# 1.net
KiCad netlist of a schematic drawn in Altium Designer
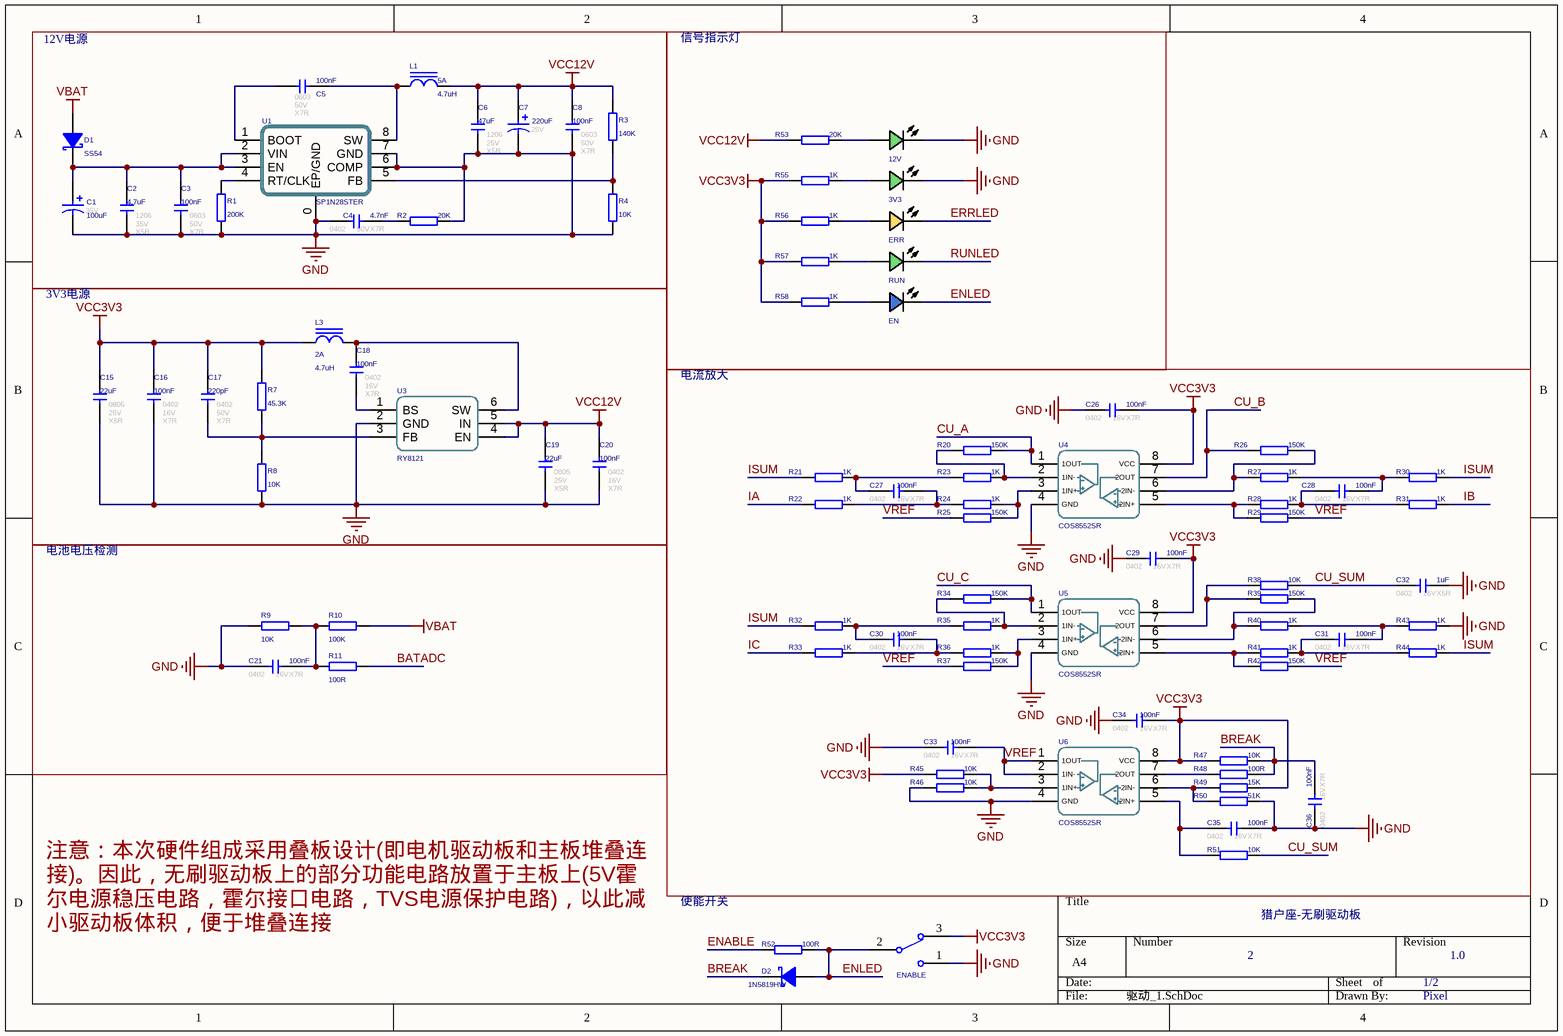
[diagram p0: 驱动_1.SchDoc]

(export (version "E")
  (design (tool "Eeschema 10.0.6"))
  (components
    (comp (ref "3V3")
      (value "翠绿贴片LED")
      (footprint "LEDC1608(0603)-L")
      (fields (field (name "PUBLISHER") "Altium Limited"))
      (libsource (lib "无刷驱动-Infineon-AUIRS2181S-GTM-6S") (part "LED Chip Green"))
    )
    (comp (ref "12V")
      (value "翠绿贴片LED")
      (footprint "LEDC1608(0603)-L")
      (fields (field (name "PUBLISHER") "Altium Limited"))
      (libsource (lib "无刷驱动-Infineon-AUIRS2181S-GTM-6S") (part "LED Chip Green"))
    )
    (comp (ref "C1")
      (value "100uF")
      (footprint "CAP-E-S 6.3")
      (description "贴片电解电容 100uF 35V 6.3x7.7")
      (fields (field (name "VOLTAGE") "35V") (field (name "Comment") "100uF 35V 铝电解"))
      (libsource (lib "无刷驱动-Infineon-AUIRS2181S-GTM-6S") (part "E-S 100uF 35V 6.3x7.7"))
    )
    (comp (ref "C2")
      (value "4.7uF")
      (footprint "1206")
      (description "贴片瓷片电容; MLCC; 1206(3216);")
      (fields
        (field (name "VOLTAGE") "35V")
        (field (name "TYPE") "X5R")
        (field (name "Comment") "4.7uF 35V X5R")
      )
      (libsource (lib "无刷驱动-Infineon-AUIRS2181S-GTM-6S") (part "4.7uF 1206 35V X5R"))
    )
    (comp (ref "C3")
      (value "100nF")
      (footprint "0603")
      (description "贴片瓷片电容; MLCC; 0603(1608);")
      (fields
        (field (name "VOLTAGE") "50V")
        (field (name "TYPE") "X7R")
        (field (name "Comment") "100nF 50V X7R")
      )
      (libsource (lib "无刷驱动-Infineon-AUIRS2181S-GTM-6S") (part "100nF 0603 50V X7R"))
    )
    (comp (ref "C4")
      (value "4.7nF")
      (footprint "0402")
      (description "贴片瓷片电容; MLCC; 0402(1005);")
      (fields
        (field (name "VOLTAGE") "50V")
        (field (name "TYPE") "X7R")
        (field (name "Comment") "4.7nF 50V X7R")
      )
      (libsource (lib "无刷驱动-Infineon-AUIRS2181S-GTM-6S") (part "4.7nF 0402 50V X7R"))
    )
    (comp (ref "C5")
      (value "100nF")
      (footprint "0603")
      (description "贴片瓷片电容; MLCC; 0603(1608);")
      (fields
        (field (name "VOLTAGE") "50V")
        (field (name "TYPE") "X7R")
        (field (name "Comment") "100nF 50V X7R")
      )
      (libsource (lib "无刷驱动-Infineon-AUIRS2181S-GTM-6S") (part "100nF 0603 50V X7R"))
    )
    (comp (ref "C6")
      (value "47uF")
      (footprint "1206")
      (description "贴片瓷片电容; MLCC; 1206(3216);")
      (fields
        (field (name "VOLTAGE") "25V")
        (field (name "TYPE") "X5R")
        (field (name "Comment") "47uF 25V X5R")
      )
      (libsource (lib "无刷驱动-Infineon-AUIRS2181S-GTM-6S") (part "47uF 1206 25V X5R"))
    )
    (comp (ref "C7")
      (value "220uF")
      (footprint "CAP-E-S 6.3")
      (description "贴片电解电容 220uF 25V 6.3x7.7")
      (fields (field (name "VOLTAGE") "25V") (field (name "Comment") "220uF 25V 铝电解"))
      (libsource (lib "无刷驱动-Infineon-AUIRS2181S-GTM-6S") (part "E-S 220uF 25V 6.3x7.7"))
    )
    (comp (ref "C8")
      (value "100nF")
      (footprint "0603")
      (description "贴片瓷片电容; MLCC; 0603(1608);")
      (fields
        (field (name "VOLTAGE") "50V")
        (field (name "TYPE") "X7R")
        (field (name "Comment") "100nF 50V X7R")
      )
      (libsource (lib "无刷驱动-Infineon-AUIRS2181S-GTM-6S") (part "100nF 0603 50V X7R"))
    )
    (comp (ref "C15")
      (value "22uF")
      (footprint "0805")
      (description "贴片瓷片电容; MLCC; 0805(2012);")
      (fields
        (field (name "VOLTAGE") "25V")
        (field (name "TYPE") "X5R")
        (field (name "Comment") "22uF 25V X5R")
      )
      (libsource (lib "无刷驱动-Infineon-AUIRS2181S-GTM-6S") (part "22uF 0805 25V X5R"))
    )
    (comp (ref "C16")
      (value "100nF")
      (footprint "0402")
      (description "贴片瓷片电容; MLCC; 0402(1005);")
      (fields
        (field (name "VOLTAGE") "16V")
        (field (name "TYPE") "X7R")
        (field (name "Comment") "100nF 16V X7R")
      )
      (libsource (lib "无刷驱动-Infineon-AUIRS2181S-GTM-6S") (part "100nF 0402 16V X7R"))
    )
    (comp (ref "C17")
      (value "220pF")
      (footprint "0402")
      (description "贴片瓷片电容; MLCC; 0402(1005);")
      (fields
        (field (name "VOLTAGE") "50V")
        (field (name "TYPE") "X7R")
        (field (name "Comment") "220pF 50V X7R")
      )
      (libsource (lib "无刷驱动-Infineon-AUIRS2181S-GTM-6S") (part "220pF 0402 50V X7R"))
    )
    (comp (ref "C18")
      (value "100nF")
      (footprint "0402")
      (description "贴片瓷片电容; MLCC; 0402(1005);")
      (fields
        (field (name "VOLTAGE") "16V")
        (field (name "TYPE") "X7R")
        (field (name "Comment") "100nF 16V X7R")
      )
      (libsource (lib "无刷驱动-Infineon-AUIRS2181S-GTM-6S") (part "100nF 0402 16V X7R"))
    )
    (comp (ref "C19")
      (value "22uF")
      (footprint "0805")
      (description "贴片瓷片电容; MLCC; 0805(2012);")
      (fields
        (field (name "VOLTAGE") "25V")
        (field (name "TYPE") "X5R")
        (field (name "Comment") "22uF 25V X5R")
      )
      (libsource (lib "无刷驱动-Infineon-AUIRS2181S-GTM-6S") (part "22uF 0805 25V X5R"))
    )
    (comp (ref "C20")
      (value "100nF")
      (footprint "0402")
      (description "贴片瓷片电容; MLCC; 0402(1005);")
      (fields
        (field (name "VOLTAGE") "16V")
        (field (name "TYPE") "X7R")
        (field (name "Comment") "100nF 16V X7R")
      )
      (libsource (lib "无刷驱动-Infineon-AUIRS2181S-GTM-6S") (part "100nF 0402 16V X7R"))
    )
    (comp (ref "C21")
      (value "100nF")
      (footprint "0402")
      (description "贴片瓷片电容; MLCC; 0402(1005);")
      (fields
        (field (name "VOLTAGE") "16V")
        (field (name "TYPE") "X7R")
        (field (name "Comment") "100nF 16V X7R")
      )
      (libsource (lib "无刷驱动-Infineon-AUIRS2181S-GTM-6S") (part "100nF 0402 16V X7R"))
    )
    (comp (ref "C26")
      (value "100nF")
      (footprint "0402")
      (description "贴片瓷片电容; MLCC; 0402(1005);")
      (fields
        (field (name "VOLTAGE") "16V")
        (field (name "TYPE") "X7R")
        (field (name "Comment") "100nF 16V X7R")
      )
      (libsource (lib "无刷驱动-Infineon-AUIRS2181S-GTM-6S") (part "100nF 0402 16V X7R"))
    )
    (comp (ref "C27")
      (value "100nF")
      (footprint "0402")
      (description "贴片瓷片电容; MLCC; 0402(1005);")
      (fields
        (field (name "VOLTAGE") "16V")
        (field (name "TYPE") "X7R")
        (field (name "Comment") "100nF 16V X7R")
      )
      (libsource (lib "无刷驱动-Infineon-AUIRS2181S-GTM-6S") (part "100nF 0402 16V X7R"))
    )
    (comp (ref "C28")
      (value "100nF")
      (footprint "0402")
      (description "贴片瓷片电容; MLCC; 0402(1005);")
      (fields
        (field (name "VOLTAGE") "16V")
        (field (name "TYPE") "X7R")
        (field (name "Comment") "100nF 16V X7R")
      )
      (libsource (lib "无刷驱动-Infineon-AUIRS2181S-GTM-6S") (part "100nF 0402 16V X7R"))
    )
    (comp (ref "C29")
      (value "100nF")
      (footprint "0402")
      (description "贴片瓷片电容; MLCC; 0402(1005);")
      (fields
        (field (name "VOLTAGE") "16V")
        (field (name "TYPE") "X7R")
        (field (name "Comment") "100nF 16V X7R")
      )
      (libsource (lib "无刷驱动-Infineon-AUIRS2181S-GTM-6S") (part "100nF 0402 16V X7R"))
    )
    (comp (ref "C30")
      (value "100nF")
      (footprint "0402")
      (description "贴片瓷片电容; MLCC; 0402(1005);")
      (fields
        (field (name "VOLTAGE") "16V")
        (field (name "TYPE") "X7R")
        (field (name "Comment") "100nF 16V X7R")
      )
      (libsource (lib "无刷驱动-Infineon-AUIRS2181S-GTM-6S") (part "100nF 0402 16V X7R"))
    )
    (comp (ref "C31")
      (value "100nF")
      (footprint "0402")
      (description "贴片瓷片电容; MLCC; 0402(1005);")
      (fields
        (field (name "VOLTAGE") "16V")
        (field (name "TYPE") "X7R")
        (field (name "Comment") "100nF 16V X7R")
      )
      (libsource (lib "无刷驱动-Infineon-AUIRS2181S-GTM-6S") (part "100nF 0402 16V X7R"))
    )
    (comp (ref "C32")
      (value "1uF")
      (footprint "0402")
      (description "贴片瓷片电容; MLCC; 0402(1005);")
      (fields
        (field (name "VOLTAGE") "16V")
        (field (name "TYPE") "X5R")
        (field (name "Comment") "1uF 16V X5R")
      )
      (libsource (lib "无刷驱动-Infineon-AUIRS2181S-GTM-6S") (part "1uF 0402 16V X5R"))
    )
    (comp (ref "C33")
      (value "100nF")
      (footprint "0402")
      (description "贴片瓷片电容; MLCC; 0402(1005);")
      (fields
        (field (name "VOLTAGE") "16V")
        (field (name "TYPE") "X7R")
        (field (name "Comment") "100nF 16V X7R")
      )
      (libsource (lib "无刷驱动-Infineon-AUIRS2181S-GTM-6S") (part "100nF 0402 16V X7R"))
    )
    (comp (ref "C34")
      (value "100nF")
      (footprint "0402")
      (description "贴片瓷片电容; MLCC; 0402(1005);")
      (fields
        (field (name "VOLTAGE") "16V")
        (field (name "TYPE") "X7R")
        (field (name "Comment") "100nF 16V X7R")
      )
      (libsource (lib "无刷驱动-Infineon-AUIRS2181S-GTM-6S") (part "100nF 0402 16V X7R"))
    )
    (comp (ref "C35")
      (value "100nF")
      (footprint "0402")
      (description "贴片瓷片电容; MLCC; 0402(1005);")
      (fields
        (field (name "VOLTAGE") "16V")
        (field (name "TYPE") "X7R")
        (field (name "Comment") "100nF 16V X7R")
      )
      (libsource (lib "无刷驱动-Infineon-AUIRS2181S-GTM-6S") (part "100nF 0402 16V X7R"))
    )
    (comp (ref "C36")
      (value "100nF")
      (footprint "0402")
      (description "贴片瓷片电容; MLCC; 0402(1005);")
      (fields
        (field (name "VOLTAGE") "16V")
        (field (name "TYPE") "X7R")
        (field (name "Comment") "100nF 16V X7R")
      )
      (libsource (lib "无刷驱动-Infineon-AUIRS2181S-GTM-6S") (part "100nF 0402 16V X7R"))
    )
    (comp (ref "D1")
      (value "SS54")
      (footprint "SMA-L[DO-214AC]")
      (description "SS54 肖特基二极管")
      (libsource (lib "无刷驱动-Infineon-AUIRS2181S-GTM-6S") (part "SS54"))
    )
    (comp (ref "D2")
      (value "1N5819HW")
      (footprint "SOD-123-L")
      (description "1N5819HW 肖特基二极管")
      (libsource (lib "无刷驱动-Infineon-AUIRS2181S-GTM-6S") (part "1N5819HW"))
    )
    (comp (ref "EN")
      (value "蓝色贴片LED")
      (footprint "LEDC1608(0603)-L")
      (fields (field (name "PUBLISHER") "Altium Limited"))
      (libsource (lib "无刷驱动-Infineon-AUIRS2181S-GTM-6S") (part "LED Chip Blue"))
    )
    (comp (ref "ENABLE")
      (value "SW-SPDT")
      (footprint "SS12D10")
      (description "单刀双掷开关 3脚船型、钮子、拨动开关 SPDT Subminiature Toggle Switch")
      (fields (field (name "PUBLISHER") "Altium Limited"))
      (libsource (lib "无刷驱动-Infineon-AUIRS2181S-GTM-6S") (part "SW-SPDT"))
    )
    (comp (ref "ERR")
      (value "黄色贴片LED")
      (footprint "LEDC1608(0603)-L")
      (fields (field (name "PUBLISHER") "Altium Limited"))
      (libsource (lib "无刷驱动-Infineon-AUIRS2181S-GTM-6S") (part "LED Chip Yellow"))
    )
    (comp (ref "L1")
      (value "4.7uH")
      (footprint "SLO2520")
      (description "功率电感")
      (fields
        (field (name "IMAX") "5A")
        (field (name "Comment") "4.7uH 5A")
        (field (name "PUBLISHER") "Altium Limited")
      )
      (libsource (lib "无刷驱动-Infineon-AUIRS2181S-GTM-6S") (part "Ind-Power"))
    )
    (comp (ref "L3")
      (value "4.7uH")
      (footprint "SLO2520")
      (description "功率电感")
      (fields
        (field (name "IMAX") "2A")
        (field (name "Comment") "4.7uH 2A")
        (field (name "PUBLISHER") "Altium Limited")
      )
      (libsource (lib "无刷驱动-Infineon-AUIRS2181S-GTM-6S") (part "Ind-Power"))
    )
    (comp (ref "R1")
      (value "200K")
      (footprint "RESC1005[0402]S-N")
      (description "贴片电阻")
      (fields (field (name "POWER") "1/8W") (field (name "TOLERANCE") "±1%"))
      (libsource (lib "无刷驱动-Infineon-AUIRS2181S-GTM-6S") (part "Res-Chip_10"))
    )
    (comp (ref "R2")
      (value "20K")
      (footprint "RESC1005[0402]S-N")
      (description "贴片电阻")
      (fields (field (name "POWER") "1/8W") (field (name "TOLERANCE") "±1%"))
      (libsource (lib "无刷驱动-Infineon-AUIRS2181S-GTM-6S") (part "Res-Chip_7"))
    )
    (comp (ref "R3")
      (value "140K")
      (footprint "RESC1005[0402]S-N")
      (description "贴片电阻")
      (fields (field (name "POWER") "1/8W") (field (name "TOLERANCE") "±1%"))
      (libsource (lib "无刷驱动-Infineon-AUIRS2181S-GTM-6S") (part "Res-Chip_11"))
    )
    (comp (ref "R4")
      (value "10K")
      (footprint "RESC1005[0402]S-N")
      (description "贴片电阻")
      (fields (field (name "POWER") "1/8W") (field (name "TOLERANCE") "±1%"))
      (libsource (lib "无刷驱动-Infineon-AUIRS2181S-GTM-6S") (part "Res-Chip_1"))
    )
    (comp (ref "R7")
      (value "45.3K")
      (footprint "RESC1005[0402]S-N")
      (description "贴片电阻")
      (fields (field (name "POWER") "1/8W") (field (name "TOLERANCE") "±1%"))
      (libsource (lib "无刷驱动-Infineon-AUIRS2181S-GTM-6S") (part "Res-Chip_12"))
    )
    (comp (ref "R8")
      (value "10K")
      (footprint "RESC1005[0402]S-N")
      (description "贴片电阻")
      (fields (field (name "POWER") "1/8W") (field (name "TOLERANCE") "±1%"))
      (libsource (lib "无刷驱动-Infineon-AUIRS2181S-GTM-6S") (part "Res-Chip_1"))
    )
    (comp (ref "R9")
      (value "10K")
      (footprint "RESC1005[0402]S-N")
      (description "贴片电阻")
      (fields (field (name "POWER") "1/8W") (field (name "TOLERANCE") "±1%"))
      (libsource (lib "无刷驱动-Infineon-AUIRS2181S-GTM-6S") (part "Res-Chip_1"))
    )
    (comp (ref "R10")
      (value "100K")
      (footprint "RESC1005[0402]S-N")
      (description "贴片电阻")
      (fields (field (name "POWER") "1/8W") (field (name "TOLERANCE") "±1%"))
      (libsource (lib "无刷驱动-Infineon-AUIRS2181S-GTM-6S") (part "Res-Chip_9"))
    )
    (comp (ref "R11")
      (value "100R")
      (footprint "RESC1005[0402]S-N")
      (description "贴片电阻")
      (fields (field (name "POWER") "1/8W") (field (name "TOLERANCE") "±1%"))
      (libsource (lib "无刷驱动-Infineon-AUIRS2181S-GTM-6S") (part "Res-Chip_5"))
    )
    (comp (ref "R20")
      (value "150K")
      (footprint "RESC1005[0402]S-N")
      (description "贴片电阻")
      (fields (field (name "POWER") "1/8W") (field (name "TOLERANCE") "±1%"))
      (libsource (lib "无刷驱动-Infineon-AUIRS2181S-GTM-6S") (part "Res-Chip_13"))
    )
    (comp (ref "R21")
      (value "1K")
      (footprint "RESC1005[0402]S-N")
      (description "贴片电阻")
      (fields (field (name "POWER") "1/8W") (field (name "TOLERANCE") "±1%"))
      (libsource (lib "无刷驱动-Infineon-AUIRS2181S-GTM-6S") (part "Res-Chip_6"))
    )
    (comp (ref "R22")
      (value "1K")
      (footprint "RESC1005[0402]S-N")
      (description "贴片电阻")
      (fields (field (name "POWER") "1/8W") (field (name "TOLERANCE") "±1%"))
      (libsource (lib "无刷驱动-Infineon-AUIRS2181S-GTM-6S") (part "Res-Chip_6"))
    )
    (comp (ref "R23")
      (value "1K")
      (footprint "RESC1005[0402]S-N")
      (description "贴片电阻")
      (fields (field (name "POWER") "1/8W") (field (name "TOLERANCE") "±1%"))
      (libsource (lib "无刷驱动-Infineon-AUIRS2181S-GTM-6S") (part "Res-Chip_6"))
    )
    (comp (ref "R24")
      (value "1K")
      (footprint "RESC1005[0402]S-N")
      (description "贴片电阻")
      (fields (field (name "POWER") "1/8W") (field (name "TOLERANCE") "±1%"))
      (libsource (lib "无刷驱动-Infineon-AUIRS2181S-GTM-6S") (part "Res-Chip_6"))
    )
    (comp (ref "R25")
      (value "150K")
      (footprint "RESC1005[0402]S-N")
      (description "贴片电阻")
      (fields (field (name "POWER") "1/8W") (field (name "TOLERANCE") "±1%"))
      (libsource (lib "无刷驱动-Infineon-AUIRS2181S-GTM-6S") (part "Res-Chip_13"))
    )
    (comp (ref "R26")
      (value "150K")
      (footprint "RESC1005[0402]S-N")
      (description "贴片电阻")
      (fields (field (name "POWER") "1/8W") (field (name "TOLERANCE") "±1%"))
      (libsource (lib "无刷驱动-Infineon-AUIRS2181S-GTM-6S") (part "Res-Chip_13"))
    )
    (comp (ref "R27")
      (value "1K")
      (footprint "RESC1005[0402]S-N")
      (description "贴片电阻")
      (fields (field (name "POWER") "1/8W") (field (name "TOLERANCE") "±1%"))
      (libsource (lib "无刷驱动-Infineon-AUIRS2181S-GTM-6S") (part "Res-Chip_6"))
    )
    (comp (ref "R28")
      (value "1K")
      (footprint "RESC1005[0402]S-N")
      (description "贴片电阻")
      (fields (field (name "POWER") "1/8W") (field (name "TOLERANCE") "±1%"))
      (libsource (lib "无刷驱动-Infineon-AUIRS2181S-GTM-6S") (part "Res-Chip_6"))
    )
    (comp (ref "R29")
      (value "150K")
      (footprint "RESC1005[0402]S-N")
      (description "贴片电阻")
      (fields (field (name "POWER") "1/8W") (field (name "TOLERANCE") "±1%"))
      (libsource (lib "无刷驱动-Infineon-AUIRS2181S-GTM-6S") (part "Res-Chip_13"))
    )
    (comp (ref "R30")
      (value "1K")
      (footprint "RESC1005[0402]S-N")
      (description "贴片电阻")
      (fields (field (name "POWER") "1/8W") (field (name "TOLERANCE") "±1%"))
      (libsource (lib "无刷驱动-Infineon-AUIRS2181S-GTM-6S") (part "Res-Chip_6"))
    )
    (comp (ref "R31")
      (value "1K")
      (footprint "RESC1005[0402]S-N")
      (description "贴片电阻")
      (fields (field (name "POWER") "1/8W") (field (name "TOLERANCE") "±1%"))
      (libsource (lib "无刷驱动-Infineon-AUIRS2181S-GTM-6S") (part "Res-Chip_6"))
    )
    (comp (ref "R32")
      (value "1K")
      (footprint "RESC1005[0402]S-N")
      (description "贴片电阻")
      (fields (field (name "POWER") "1/8W") (field (name "TOLERANCE") "±1%"))
      (libsource (lib "无刷驱动-Infineon-AUIRS2181S-GTM-6S") (part "Res-Chip_6"))
    )
    (comp (ref "R33")
      (value "1K")
      (footprint "RESC1005[0402]S-N")
      (description "贴片电阻")
      (fields (field (name "POWER") "1/8W") (field (name "TOLERANCE") "±1%"))
      (libsource (lib "无刷驱动-Infineon-AUIRS2181S-GTM-6S") (part "Res-Chip_6"))
    )
    (comp (ref "R34")
      (value "150K")
      (footprint "RESC1005[0402]S-N")
      (description "贴片电阻")
      (fields (field (name "POWER") "1/8W") (field (name "TOLERANCE") "±1%"))
      (libsource (lib "无刷驱动-Infineon-AUIRS2181S-GTM-6S") (part "Res-Chip_13"))
    )
    (comp (ref "R35")
      (value "1K")
      (footprint "RESC1005[0402]S-N")
      (description "贴片电阻")
      (fields (field (name "POWER") "1/8W") (field (name "TOLERANCE") "±1%"))
      (libsource (lib "无刷驱动-Infineon-AUIRS2181S-GTM-6S") (part "Res-Chip_6"))
    )
    (comp (ref "R36")
      (value "1K")
      (footprint "RESC1005[0402]S-N")
      (description "贴片电阻")
      (fields (field (name "POWER") "1/8W") (field (name "TOLERANCE") "±1%"))
      (libsource (lib "无刷驱动-Infineon-AUIRS2181S-GTM-6S") (part "Res-Chip_6"))
    )
    (comp (ref "R37")
      (value "150K")
      (footprint "RESC1005[0402]S-N")
      (description "贴片电阻")
      (fields (field (name "POWER") "1/8W") (field (name "TOLERANCE") "±1%"))
      (libsource (lib "无刷驱动-Infineon-AUIRS2181S-GTM-6S") (part "Res-Chip_13"))
    )
    (comp (ref "R38")
      (value "10K")
      (footprint "RESC1005[0402]S-N")
      (description "贴片电阻")
      (fields (field (name "POWER") "1/8W") (field (name "TOLERANCE") "±1%"))
      (libsource (lib "无刷驱动-Infineon-AUIRS2181S-GTM-6S") (part "Res-Chip_1"))
    )
    (comp (ref "R39")
      (value "150K")
      (footprint "RESC1005[0402]S-N")
      (description "贴片电阻")
      (fields (field (name "POWER") "1/8W") (field (name "TOLERANCE") "±1%"))
      (libsource (lib "无刷驱动-Infineon-AUIRS2181S-GTM-6S") (part "Res-Chip_13"))
    )
    (comp (ref "R40")
      (value "1K")
      (footprint "RESC1005[0402]S-N")
      (description "贴片电阻")
      (fields (field (name "POWER") "1/8W") (field (name "TOLERANCE") "±1%"))
      (libsource (lib "无刷驱动-Infineon-AUIRS2181S-GTM-6S") (part "Res-Chip_6"))
    )
    (comp (ref "R41")
      (value "1K")
      (footprint "RESC1005[0402]S-N")
      (description "贴片电阻")
      (fields (field (name "POWER") "1/8W") (field (name "TOLERANCE") "±1%"))
      (libsource (lib "无刷驱动-Infineon-AUIRS2181S-GTM-6S") (part "Res-Chip_6"))
    )
    (comp (ref "R42")
      (value "150K")
      (footprint "RESC1005[0402]S-N")
      (description "贴片电阻")
      (fields (field (name "POWER") "1/8W") (field (name "TOLERANCE") "±1%"))
      (libsource (lib "无刷驱动-Infineon-AUIRS2181S-GTM-6S") (part "Res-Chip_13"))
    )
    (comp (ref "R43")
      (value "1K")
      (footprint "RESC1005[0402]S-N")
      (description "贴片电阻")
      (fields (field (name "POWER") "1/8W") (field (name "TOLERANCE") "±1%"))
      (libsource (lib "无刷驱动-Infineon-AUIRS2181S-GTM-6S") (part "Res-Chip_6"))
    )
    (comp (ref "R44")
      (value "1K")
      (footprint "RESC1005[0402]S-N")
      (description "贴片电阻")
      (fields (field (name "POWER") "1/8W") (field (name "TOLERANCE") "±1%"))
      (libsource (lib "无刷驱动-Infineon-AUIRS2181S-GTM-6S") (part "Res-Chip_6"))
    )
    (comp (ref "R45")
      (value "10K")
      (footprint "RESC1005[0402]S-N")
      (description "贴片电阻")
      (fields (field (name "POWER") "1/8W") (field (name "TOLERANCE") "±1%"))
      (libsource (lib "无刷驱动-Infineon-AUIRS2181S-GTM-6S") (part "Res-Chip_1"))
    )
    (comp (ref "R46")
      (value "10K")
      (footprint "RESC1005[0402]S-N")
      (description "贴片电阻")
      (fields (field (name "POWER") "1/8W") (field (name "TOLERANCE") "±1%"))
      (libsource (lib "无刷驱动-Infineon-AUIRS2181S-GTM-6S") (part "Res-Chip_1"))
    )
    (comp (ref "R47")
      (value "10K")
      (footprint "RESC1005[0402]S-N")
      (description "贴片电阻")
      (fields (field (name "POWER") "1/8W") (field (name "TOLERANCE") "±1%"))
      (libsource (lib "无刷驱动-Infineon-AUIRS2181S-GTM-6S") (part "Res-Chip_1"))
    )
    (comp (ref "R48")
      (value "100R")
      (footprint "RESC1005[0402]S-N")
      (description "贴片电阻")
      (fields (field (name "POWER") "1/8W") (field (name "TOLERANCE") "±1%"))
      (libsource (lib "无刷驱动-Infineon-AUIRS2181S-GTM-6S") (part "Res-Chip_5"))
    )
    (comp (ref "R49")
      (value "15K")
      (footprint "RESC1005[0402]S-N")
      (description "贴片电阻")
      (fields (field (name "POWER") "1/8W") (field (name "TOLERANCE") "±1%"))
      (libsource (lib "无刷驱动-Infineon-AUIRS2181S-GTM-6S") (part "Res-Chip_15"))
    )
    (comp (ref "R50")
      (value "51K")
      (footprint "RESC1005[0402]S-N")
      (description "贴片电阻")
      (fields (field (name "POWER") "1/8W") (field (name "TOLERANCE") "±1%"))
      (libsource (lib "无刷驱动-Infineon-AUIRS2181S-GTM-6S") (part "Res-Chip_14"))
    )
    (comp (ref "R51")
      (value "10K")
      (footprint "RESC1005[0402]S-N")
      (description "贴片电阻")
      (fields (field (name "POWER") "1/8W") (field (name "TOLERANCE") "±1%"))
      (libsource (lib "无刷驱动-Infineon-AUIRS2181S-GTM-6S") (part "Res-Chip_1"))
    )
    (comp (ref "R52")
      (value "100R")
      (footprint "RESC1005[0402]S-N")
      (description "贴片电阻")
      (fields (field (name "POWER") "1/8W") (field (name "TOLERANCE") "±1%"))
      (libsource (lib "无刷驱动-Infineon-AUIRS2181S-GTM-6S") (part "Res-Chip_5"))
    )
    (comp (ref "R53")
      (value "20K")
      (footprint "RESC1005[0402]S-N")
      (description "贴片电阻")
      (fields (field (name "POWER") "1/8W") (field (name "TOLERANCE") "±1%"))
      (libsource (lib "无刷驱动-Infineon-AUIRS2181S-GTM-6S") (part "Res-Chip_7"))
    )
    (comp (ref "R55")
      (value "1K")
      (footprint "RESC1005[0402]S-N")
      (description "贴片电阻")
      (fields (field (name "POWER") "1/8W") (field (name "TOLERANCE") "±1%"))
      (libsource (lib "无刷驱动-Infineon-AUIRS2181S-GTM-6S") (part "Res-Chip_6"))
    )
    (comp (ref "R56")
      (value "1K")
      (footprint "RESC1005[0402]S-N")
      (description "贴片电阻")
      (fields (field (name "POWER") "1/8W") (field (name "TOLERANCE") "±1%"))
      (libsource (lib "无刷驱动-Infineon-AUIRS2181S-GTM-6S") (part "Res-Chip_6"))
    )
    (comp (ref "R57")
      (value "1K")
      (footprint "RESC1005[0402]S-N")
      (description "贴片电阻")
      (fields (field (name "POWER") "1/8W") (field (name "TOLERANCE") "±1%"))
      (libsource (lib "无刷驱动-Infineon-AUIRS2181S-GTM-6S") (part "Res-Chip_6"))
    )
    (comp (ref "R58")
      (value "1K")
      (footprint "RESC1005[0402]S-N")
      (description "贴片电阻")
      (fields (field (name "POWER") "1/8W") (field (name "TOLERANCE") "±1%"))
      (libsource (lib "无刷驱动-Infineon-AUIRS2181S-GTM-6S") (part "Res-Chip_6"))
    )
    (comp (ref "RUN")
      (value "翠绿贴片LED")
      (footprint "LEDC1608(0603)-L")
      (fields (field (name "PUBLISHER") "Altium Limited"))
      (libsource (lib "无刷驱动-Infineon-AUIRS2181S-GTM-6S") (part "LED Chip Green"))
    )
    (comp (ref "U1")
      (value "SP1N28STER")
      (footprint "SOP-8E")
      (libsource (lib "无刷驱动-Infineon-AUIRS2181S-GTM-6S") (part "SP1N28STER"))
    )
    (comp (ref "U3")
      (value "RY8121")
      (footprint "SOT-23-6")
      (description "18V 2A 1MHz Synchronous Step-Down Regulator")
      (libsource (lib "无刷驱动-Infineon-AUIRS2181S-GTM-6S") (part "RY8121"))
    )
    (comp (ref "U4")
      (value "COS8552SR")
      (footprint "SOP-8")
      (description "COS8552SR 二路通用运算放大器")
      (libsource (lib "无刷驱动-Infineon-AUIRS2181S-GTM-6S") (part "COS8552SR"))
    )
    (comp (ref "U5")
      (value "COS8552SR")
      (footprint "SOP-8")
      (description "COS8552SR 二路通用运算放大器")
      (libsource (lib "无刷驱动-Infineon-AUIRS2181S-GTM-6S") (part "COS8552SR"))
    )
    (comp (ref "U6")
      (value "COS8552SR")
      (footprint "SOP-8")
      (description "COS8552SR 二路通用运算放大器")
      (libsource (lib "无刷驱动-Infineon-AUIRS2181S-GTM-6S") (part "COS8552SR"))
    )
  )
  (nets
    (net (code "1") (name "/BATADC") (class "Default")
      (node (ref "R11") (pin "2") (pinfunction "2_2") (pintype "passive"))
    )
    (net (code "2") (name "/BREAK") (class "Default")
      (node (ref "C36") (pin "2") (pinfunction "2_2") (pintype "passive"))
      (node (ref "D2") (pin "K") (pinfunction "K_K") (pintype "passive"))
      (node (ref "R47") (pin "2") (pinfunction "2_2") (pintype "passive"))
      (node (ref "R48") (pin "2") (pinfunction "2_2") (pintype "passive"))
    )
    (net (code "3") (name "/CU_A") (class "Default")
      (node (ref "R20") (pin "2") (pinfunction "2_2") (pintype "passive"))
      (node (ref "U4") (pin "1") (pinfunction "1OUT_1") (pintype "passive"))
    )
    (net (code "4") (name "/CU_B") (class "Default")
      (node (ref "R26") (pin "2") (pinfunction "2_2") (pintype "passive"))
      (node (ref "U4") (pin "7") (pinfunction "2OUT_7") (pintype "passive"))
    )
    (net (code "5") (name "/CU_C") (class "Default")
      (node (ref "R34") (pin "2") (pinfunction "2_2") (pintype "passive"))
      (node (ref "U5") (pin "1") (pinfunction "1OUT_1") (pintype "passive"))
    )
    (net (code "6") (name "/CU_SUM") (class "Default")
      (node (ref "C32") (pin "1") (pinfunction "1_1") (pintype "passive"))
      (node (ref "R38") (pin "2") (pinfunction "2_2") (pintype "passive"))
      (node (ref "R51") (pin "2") (pinfunction "2_2") (pintype "passive"))
    )
    (net (code "7") (name "/ENABLE") (class "Default")
      (node (ref "R52") (pin "1") (pinfunction "1_1") (pintype "passive"))
    )
    (net (code "8") (name "/ENLED") (class "Default")
      (node (ref "D2") (pin "A") (pinfunction "A_A") (pintype "passive"))
      (node (ref "EN") (pin "C") (pinfunction "C_C") (pintype "passive"))
      (node (ref "ENABLE") (pin "2") (pintype "passive"))
      (node (ref "R52") (pin "2") (pinfunction "2_2") (pintype "passive"))
    )
    (net (code "9") (name "/ERRLED") (class "Default")
      (node (ref "ERR") (pin "C") (pinfunction "C_C") (pintype "passive"))
    )
    (net (code "10") (name "/IA") (class "Default")
      (node (ref "R22") (pin "1") (pinfunction "1_1") (pintype "passive"))
    )
    (net (code "11") (name "/IB") (class "Default")
      (node (ref "R31") (pin "1") (pinfunction "1_1") (pintype "passive"))
    )
    (net (code "12") (name "/IC") (class "Default")
      (node (ref "R33") (pin "1") (pinfunction "1_1") (pintype "passive"))
    )
    (net (code "13") (name "/ISUM") (class "Default")
      (node (ref "R21") (pin "1") (pinfunction "1_1") (pintype "passive"))
      (node (ref "R30") (pin "1") (pinfunction "1_1") (pintype "passive"))
      (node (ref "R32") (pin "1") (pinfunction "1_1") (pintype "passive"))
      (node (ref "R44") (pin "1") (pinfunction "1_1") (pintype "passive"))
    )
    (net (code "14") (name "/RUNLED") (class "Default")
      (node (ref "RUN") (pin "C") (pinfunction "C_C") (pintype "passive"))
    )
    (net (code "15") (name "/VREF") (class "Default")
      (node (ref "C33") (pin "2") (pinfunction "2_2") (pintype "passive"))
      (node (ref "R25") (pin "1") (pinfunction "1_1") (pintype "passive"))
      (node (ref "R29") (pin "1") (pinfunction "1_1") (pintype "passive"))
      (node (ref "R37") (pin "1") (pinfunction "1_1") (pintype "passive"))
      (node (ref "R42") (pin "1") (pinfunction "1_1") (pintype "passive"))
      (node (ref "U6") (pin "1") (pinfunction "1OUT_1") (pintype "passive"))
      (node (ref "U6") (pin "2") (pinfunction "1IN-_2") (pintype "passive"))
    )
    (net (code "16") (name "GND") (class "Default")
      (node (ref "12V") (pin "C") (pinfunction "C_C") (pintype "passive"))
      (node (ref "3V3") (pin "C") (pinfunction "C_C") (pintype "passive"))
      (node (ref "C1") (pin "2") (pinfunction "2_2") (pintype "passive"))
      (node (ref "C15") (pin "1") (pinfunction "1_1") (pintype "passive"))
      (node (ref "C16") (pin "1") (pinfunction "1_1") (pintype "passive"))
      (node (ref "C19") (pin "1") (pinfunction "1_1") (pintype "passive"))
      (node (ref "C2") (pin "1") (pinfunction "1_1") (pintype "passive"))
      (node (ref "C20") (pin "1") (pinfunction "1_1") (pintype "passive"))
      (node (ref "C21") (pin "1") (pinfunction "1_1") (pintype "passive"))
      (node (ref "C26") (pin "1") (pinfunction "1_1") (pintype "passive"))
      (node (ref "C29") (pin "1") (pinfunction "1_1") (pintype "passive"))
      (node (ref "C3") (pin "1") (pinfunction "1_1") (pintype "passive"))
      (node (ref "C32") (pin "2") (pinfunction "2_2") (pintype "passive"))
      (node (ref "C33") (pin "1") (pinfunction "1_1") (pintype "passive"))
      (node (ref "C34") (pin "1") (pinfunction "1_1") (pintype "passive"))
      (node (ref "C35") (pin "2") (pinfunction "2_2") (pintype "passive"))
      (node (ref "C36") (pin "1") (pinfunction "1_1") (pintype "passive"))
      (node (ref "C4") (pin "1") (pinfunction "1_1") (pintype "passive"))
      (node (ref "C6") (pin "1") (pinfunction "1_1") (pintype "passive"))
      (node (ref "C7") (pin "2") (pinfunction "2_2") (pintype "passive"))
      (node (ref "C8") (pin "1") (pinfunction "1_1") (pintype "passive"))
      (node (ref "ENABLE") (pin "1") (pintype "passive"))
      (node (ref "R1") (pin "1") (pinfunction "1_1") (pintype "passive"))
      (node (ref "R2") (pin "2") (pinfunction "2_2") (pintype "passive"))
      (node (ref "R4") (pin "1") (pinfunction "1_1") (pintype "passive"))
      (node (ref "R43") (pin "1") (pinfunction "1_1") (pintype "passive"))
      (node (ref "R46") (pin "1") (pinfunction "1_1") (pintype "passive"))
      (node (ref "R50") (pin "2") (pinfunction "2_2") (pintype "passive"))
      (node (ref "R8") (pin "1") (pinfunction "1_1") (pintype "passive"))
      (node (ref "R9") (pin "1") (pinfunction "1_1") (pintype "passive"))
      (node (ref "U1") (pin "0") (pinfunction "EP/GND_0") (pintype "passive"))
      (node (ref "U1") (pin "6") (pinfunction "COMP_6") (pintype "passive"))
      (node (ref "U1") (pin "7") (pinfunction "GND_7") (pintype "passive"))
      (node (ref "U3") (pin "2") (pinfunction "GND_2") (pintype "passive"))
      (node (ref "U4") (pin "4") (pinfunction "GND_4") (pintype "passive"))
      (node (ref "U5") (pin "4") (pinfunction "GND_4") (pintype "passive"))
      (node (ref "U6") (pin "4") (pinfunction "GND_4") (pintype "passive"))
    )
    (net (code "17") (name "Net-(3V3-PadA)") (class "Default")
      (node (ref "3V3") (pin "A") (pinfunction "A_A") (pintype "passive"))
      (node (ref "R55") (pin "2") (pinfunction "2_2") (pintype "passive"))
    )
    (net (code "18") (name "Net-(12V-PadA)") (class "Default")
      (node (ref "12V") (pin "A") (pinfunction "A_A") (pintype "passive"))
      (node (ref "R53") (pin "2") (pinfunction "2_2") (pintype "passive"))
    )
    (net (code "19") (name "Net-(C4-Pad2)") (class "Default")
      (node (ref "C4") (pin "2") (pinfunction "2_2") (pintype "passive"))
      (node (ref "R2") (pin "1") (pinfunction "1_1") (pintype "passive"))
    )
    (net (code "20") (name "Net-(C21-Pad2)") (class "Default")
      (node (ref "C21") (pin "2") (pinfunction "2_2") (pintype "passive"))
      (node (ref "R10") (pin "1") (pinfunction "1_1") (pintype "passive"))
      (node (ref "R11") (pin "1") (pinfunction "1_1") (pintype "passive"))
      (node (ref "R9") (pin "2") (pinfunction "2_2") (pintype "passive"))
    )
    (net (code "21") (name "Net-(C27-Pad1)") (class "Default")
      (node (ref "C27") (pin "1") (pinfunction "1_1") (pintype "passive"))
      (node (ref "R21") (pin "2") (pinfunction "2_2") (pintype "passive"))
      (node (ref "R23") (pin "1") (pinfunction "1_1") (pintype "passive"))
    )
    (net (code "22") (name "Net-(C27-Pad2)") (class "Default")
      (node (ref "C27") (pin "2") (pinfunction "2_2") (pintype "passive"))
      (node (ref "R22") (pin "2") (pinfunction "2_2") (pintype "passive"))
      (node (ref "R24") (pin "1") (pinfunction "1_1") (pintype "passive"))
    )
    (net (code "23") (name "Net-(C28-Pad1)") (class "Default")
      (node (ref "C28") (pin "1") (pinfunction "1_1") (pintype "passive"))
      (node (ref "R27") (pin "1") (pinfunction "1_1") (pintype "passive"))
      (node (ref "R30") (pin "2") (pinfunction "2_2") (pintype "passive"))
    )
    (net (code "24") (name "Net-(C28-Pad2)") (class "Default")
      (node (ref "C28") (pin "2") (pinfunction "2_2") (pintype "passive"))
      (node (ref "R28") (pin "1") (pinfunction "1_1") (pintype "passive"))
      (node (ref "R31") (pin "2") (pinfunction "2_2") (pintype "passive"))
    )
    (net (code "25") (name "Net-(C30-Pad1)") (class "Default")
      (node (ref "C30") (pin "1") (pinfunction "1_1") (pintype "passive"))
      (node (ref "R32") (pin "2") (pinfunction "2_2") (pintype "passive"))
      (node (ref "R35") (pin "1") (pinfunction "1_1") (pintype "passive"))
    )
    (net (code "26") (name "Net-(C30-Pad2)") (class "Default")
      (node (ref "C30") (pin "2") (pinfunction "2_2") (pintype "passive"))
      (node (ref "R33") (pin "2") (pinfunction "2_2") (pintype "passive"))
      (node (ref "R36") (pin "1") (pinfunction "1_1") (pintype "passive"))
    )
    (net (code "27") (name "Net-(C31-Pad1)") (class "Default")
      (node (ref "C31") (pin "1") (pinfunction "1_1") (pintype "passive"))
      (node (ref "R40") (pin "1") (pinfunction "1_1") (pintype "passive"))
      (node (ref "R43") (pin "2") (pinfunction "2_2") (pintype "passive"))
    )
    (net (code "28") (name "Net-(C31-Pad2)") (class "Default")
      (node (ref "C31") (pin "2") (pinfunction "2_2") (pintype "passive"))
      (node (ref "R41") (pin "1") (pinfunction "1_1") (pintype "passive"))
      (node (ref "R44") (pin "2") (pinfunction "2_2") (pintype "passive"))
    )
    (net (code "29") (name "Net-(EN-PadA)") (class "Default")
      (node (ref "EN") (pin "A") (pinfunction "A_A") (pintype "passive"))
      (node (ref "R58") (pin "2") (pinfunction "2_2") (pintype "passive"))
    )
    (net (code "30") (name "Net-(ERR-PadA)") (class "Default")
      (node (ref "ERR") (pin "A") (pinfunction "A_A") (pintype "passive"))
      (node (ref "R56") (pin "2") (pinfunction "2_2") (pintype "passive"))
    )
    (net (code "31") (name "Net-(R57-Pad2)") (class "Default")
      (node (ref "R57") (pin "2") (pinfunction "2_2") (pintype "passive"))
      (node (ref "RUN") (pin "A") (pinfunction "A_A") (pintype "passive"))
    )
    (net (code "32") (name "Net-(U1-BOOT)") (class "Default")
      (node (ref "C5") (pin "1") (pinfunction "1_1") (pintype "passive"))
      (node (ref "U1") (pin "1") (pinfunction "BOOT_1") (pintype "passive"))
    )
    (net (code "33") (name "Net-(U1-EN)") (class "Default")
      (node (ref "C1") (pin "1") (pinfunction "1_1") (pintype "passive"))
      (node (ref "C2") (pin "2") (pinfunction "2_2") (pintype "passive"))
      (node (ref "C3") (pin "2") (pinfunction "2_2") (pintype "passive"))
      (node (ref "D1") (pin "K") (pinfunction "K_K") (pintype "passive"))
      (node (ref "U1") (pin "2") (pinfunction "VIN_2") (pintype "passive"))
      (node (ref "U1") (pin "3") (pinfunction "EN_3") (pintype "passive"))
    )
    (net (code "34") (name "Net-(U1-FB)") (class "Default")
      (node (ref "R3") (pin "1") (pinfunction "1_1") (pintype "passive"))
      (node (ref "R4") (pin "2") (pinfunction "2_2") (pintype "passive"))
      (node (ref "U1") (pin "5") (pinfunction "FB_5") (pintype "passive"))
    )
    (net (code "35") (name "Net-(U1-RT{slash}CLK)") (class "Default")
      (node (ref "R1") (pin "2") (pinfunction "2_2") (pintype "passive"))
      (node (ref "U1") (pin "4") (pinfunction "RT/CLK_4") (pintype "passive"))
    )
    (net (code "36") (name "Net-(U1-SW)") (class "Default")
      (node (ref "C5") (pin "2") (pinfunction "2_2") (pintype "passive"))
      (node (ref "L1") (pin "1") (pinfunction "1_1") (pintype "passive"))
      (node (ref "U1") (pin "8") (pinfunction "SW_8") (pintype "passive"))
    )
    (net (code "37") (name "Net-(U3-BS)") (class "Default")
      (node (ref "C18") (pin "1") (pinfunction "1_1") (pintype "passive"))
      (node (ref "U3") (pin "1") (pinfunction "BS_1") (pintype "passive"))
    )
    (net (code "38") (name "Net-(U3-FB)") (class "Default")
      (node (ref "C17") (pin "1") (pinfunction "1_1") (pintype "passive"))
      (node (ref "R7") (pin "1") (pinfunction "1_1") (pintype "passive"))
      (node (ref "R8") (pin "2") (pinfunction "2_2") (pintype "passive"))
      (node (ref "U3") (pin "3") (pinfunction "FB_3") (pintype "passive"))
    )
    (net (code "39") (name "Net-(U3-SW)") (class "Default")
      (node (ref "C18") (pin "2") (pinfunction "2_2") (pintype "passive"))
      (node (ref "L3") (pin "2") (pinfunction "2_2") (pintype "passive"))
      (node (ref "U3") (pin "6") (pinfunction "SW_6") (pintype "passive"))
    )
    (net (code "40") (name "Net-(U4-1IN+)") (class "Default")
      (node (ref "R24") (pin "2") (pinfunction "2_2") (pintype "passive"))
      (node (ref "R25") (pin "2") (pinfunction "2_2") (pintype "passive"))
      (node (ref "U4") (pin "3") (pinfunction "1IN+_3") (pintype "passive"))
    )
    (net (code "41") (name "Net-(U4-1IN-)") (class "Default")
      (node (ref "R20") (pin "1") (pinfunction "1_1") (pintype "passive"))
      (node (ref "R23") (pin "2") (pinfunction "2_2") (pintype "passive"))
      (node (ref "U4") (pin "2") (pinfunction "1IN-_2") (pintype "passive"))
    )
    (net (code "42") (name "Net-(U4-2IN+)") (class "Default")
      (node (ref "R28") (pin "2") (pinfunction "2_2") (pintype "passive"))
      (node (ref "R29") (pin "2") (pinfunction "2_2") (pintype "passive"))
      (node (ref "U4") (pin "5") (pinfunction "2IN+_5") (pintype "passive"))
    )
    (net (code "43") (name "Net-(U4-2IN-)") (class "Default")
      (node (ref "R26") (pin "1") (pinfunction "1_1") (pintype "passive"))
      (node (ref "R27") (pin "2") (pinfunction "2_2") (pintype "passive"))
      (node (ref "U4") (pin "6") (pinfunction "2IN-_6") (pintype "passive"))
    )
    (net (code "44") (name "Net-(U5-1IN+)") (class "Default")
      (node (ref "R36") (pin "2") (pinfunction "2_2") (pintype "passive"))
      (node (ref "R37") (pin "2") (pinfunction "2_2") (pintype "passive"))
      (node (ref "U5") (pin "3") (pinfunction "1IN+_3") (pintype "passive"))
    )
    (net (code "45") (name "Net-(U5-1IN-)") (class "Default")
      (node (ref "R34") (pin "1") (pinfunction "1_1") (pintype "passive"))
      (node (ref "R35") (pin "2") (pinfunction "2_2") (pintype "passive"))
      (node (ref "U5") (pin "2") (pinfunction "1IN-_2") (pintype "passive"))
    )
    (net (code "46") (name "Net-(U5-2IN+)") (class "Default")
      (node (ref "R41") (pin "2") (pinfunction "2_2") (pintype "passive"))
      (node (ref "R42") (pin "2") (pinfunction "2_2") (pintype "passive"))
      (node (ref "U5") (pin "5") (pinfunction "2IN+_5") (pintype "passive"))
    )
    (net (code "47") (name "Net-(U5-2IN-)") (class "Default")
      (node (ref "R39") (pin "1") (pinfunction "1_1") (pintype "passive"))
      (node (ref "R40") (pin "2") (pinfunction "2_2") (pintype "passive"))
      (node (ref "U5") (pin "6") (pinfunction "2IN-_6") (pintype "passive"))
    )
    (net (code "48") (name "Net-(U5-2OUT)") (class "Default")
      (node (ref "R38") (pin "1") (pinfunction "1_1") (pintype "passive"))
      (node (ref "R39") (pin "2") (pinfunction "2_2") (pintype "passive"))
      (node (ref "U5") (pin "7") (pinfunction "2OUT_7") (pintype "passive"))
    )
    (net (code "49") (name "Net-(U6-1IN+)") (class "Default")
      (node (ref "R45") (pin "2") (pinfunction "2_2") (pintype "passive"))
      (node (ref "R46") (pin "2") (pinfunction "2_2") (pintype "passive"))
      (node (ref "U6") (pin "3") (pinfunction "1IN+_3") (pintype "passive"))
    )
    (net (code "50") (name "Net-(U6-2IN+)") (class "Default")
      (node (ref "C35") (pin "1") (pinfunction "1_1") (pintype "passive"))
      (node (ref "R51") (pin "1") (pinfunction "1_1") (pintype "passive"))
      (node (ref "U6") (pin "5") (pinfunction "2IN+_5") (pintype "passive"))
    )
    (net (code "51") (name "Net-(U6-2IN-)") (class "Default")
      (node (ref "R49") (pin "1") (pinfunction "1_1") (pintype "passive"))
      (node (ref "R50") (pin "1") (pinfunction "1_1") (pintype "passive"))
      (node (ref "U6") (pin "6") (pinfunction "2IN-_6") (pintype "passive"))
    )
    (net (code "52") (name "Net-(U6-2OUT)") (class "Default")
      (node (ref "R48") (pin "1") (pinfunction "1_1") (pintype "passive"))
      (node (ref "U6") (pin "7") (pinfunction "2OUT_7") (pintype "passive"))
    )
    (net (code "53") (name "VBAT") (class "Default")
      (node (ref "D1") (pin "A") (pinfunction "A_A") (pintype "passive"))
      (node (ref "R10") (pin "2") (pinfunction "2_2") (pintype "passive"))
    )
    (net (code "54") (name "VCC3V3") (class "Default")
      (node (ref "C15") (pin "2") (pinfunction "2_2") (pintype "passive"))
      (node (ref "C16") (pin "2") (pinfunction "2_2") (pintype "passive"))
      (node (ref "C17") (pin "2") (pinfunction "2_2") (pintype "passive"))
      (node (ref "C26") (pin "2") (pinfunction "2_2") (pintype "passive"))
      (node (ref "C29") (pin "2") (pinfunction "2_2") (pintype "passive"))
      (node (ref "C34") (pin "2") (pinfunction "2_2") (pintype "passive"))
      (node (ref "ENABLE") (pin "3") (pintype "passive"))
      (node (ref "L3") (pin "1") (pinfunction "1_1") (pintype "passive"))
      (node (ref "R45") (pin "1") (pinfunction "1_1") (pintype "passive"))
      (node (ref "R47") (pin "1") (pinfunction "1_1") (pintype "passive"))
      (node (ref "R49") (pin "2") (pinfunction "2_2") (pintype "passive"))
      (node (ref "R55") (pin "1") (pinfunction "1_1") (pintype "passive"))
      (node (ref "R56") (pin "1") (pinfunction "1_1") (pintype "passive"))
      (node (ref "R57") (pin "1") (pinfunction "1_1") (pintype "passive"))
      (node (ref "R58") (pin "1") (pinfunction "1_1") (pintype "passive"))
      (node (ref "R7") (pin "2") (pinfunction "2_2") (pintype "passive"))
      (node (ref "U4") (pin "8") (pinfunction "VCC_8") (pintype "passive"))
      (node (ref "U5") (pin "8") (pinfunction "VCC_8") (pintype "passive"))
      (node (ref "U6") (pin "8") (pinfunction "VCC_8") (pintype "passive"))
    )
    (net (code "55") (name "VCC12V") (class "Default")
      (node (ref "C19") (pin "2") (pinfunction "2_2") (pintype "passive"))
      (node (ref "C20") (pin "2") (pinfunction "2_2") (pintype "passive"))
      (node (ref "C6") (pin "2") (pinfunction "2_2") (pintype "passive"))
      (node (ref "C7") (pin "1") (pinfunction "1_1") (pintype "passive"))
      (node (ref "C8") (pin "2") (pinfunction "2_2") (pintype "passive"))
      (node (ref "L1") (pin "2") (pinfunction "2_2") (pintype "passive"))
      (node (ref "R3") (pin "2") (pinfunction "2_2") (pintype "passive"))
      (node (ref "R53") (pin "1") (pinfunction "1_1") (pintype "passive"))
      (node (ref "U3") (pin "4") (pinfunction "EN_4") (pintype "passive"))
      (node (ref "U3") (pin "5") (pinfunction "IN_5") (pintype "passive"))
    )
  )
)
